# RS485_Reserved_Sensor_Socket.net
KiCad netlist of a schematic drawn in Altium Designer
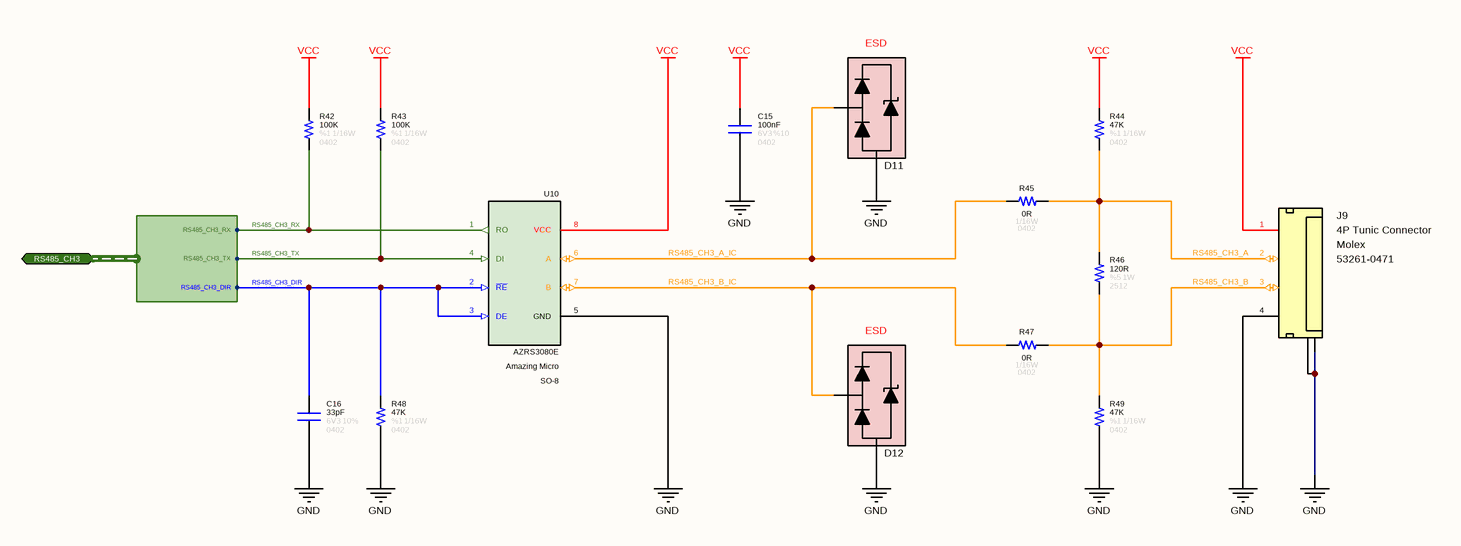
[diagram p0: RS485 Reserved Sensor Socket.SchDoc]

(export (version "E")
  (design (tool "Eeschema 10.0.6"))
  (components
    (comp (ref "C15")
      (value "100nF")
      (footprint "CAPACITOR_0402")
      (description "Capacitor - 100nF [0402-6V3] (Ceramic)")
      (fields
        (field (name "MANUFACTURER PART NUMBER") "04026D104KAT4A")
        (field (name "TOLERANCE") "%10")
        (field (name "VOLTAGE") "6V3")
        (field (name "CASE") "0402")
        (field (name "Comment") "Capacitor - 100nF [0402] (Ceramic)")
      )
      (libsource (lib "P101DA_Library") (part "Capacitor - 100nF [0402-6V3]"))
    )
    (comp (ref "C16")
      (value "33pF")
      (footprint "CAPACITOR_0402")
      (description "Capacitor - 33pF [0402] (Ceramic)")
      (fields
        (field (name "MANUFACTURER PART NUMBER") "C0402C330J9RACAUTO")
        (field (name "TOLERANCE") "10%")
        (field (name "CASE") "0402")
        (field (name "VOLTAGE") "6V3")
      )
      (libsource (lib "P101DA_Library") (part "Capacitor - 33pF [0402-6V3]"))
    )
    (comp (ref "D11")
      (value "0402ESDA-MLP1")
      (footprint "ESD_0402")
      (description "SUPPRESSOR ESD 30VDC 0402 HFREE")
      (libsource (lib "P101DA_Library") (part "Diode - TPD1E05U06DPYR"))
    )
    (comp (ref "D12")
      (value "0402ESDA-MLP1")
      (footprint "ESD_0402")
      (description "SUPPRESSOR ESD 30VDC 0402 HFREE")
      (libsource (lib "P101DA_Library") (part "Diode - TPD1E05U06DPYR"))
    )
    (comp (ref "J9")
      (value "4P SMD Tunic Connector")
      (footprint "Connector_Tunic 4P")
      (description "Mini Tunic Connector with 4P")
      (fields
        (field (name "MANUFACTURER NAME") "Molex")
        (field (name "MANUFACTURER PART NUMBER") "53261-0471")
      )
      (libsource (lib "P101DA_Library") (part "Connector - Mini Tunic 4P (1.25)"))
    )
    (comp (ref "R42")
      (value "100K")
      (footprint "RESISTOR_0402")
      (description "Thick Film Resistors - SMD 1/16 W 100 KOhm 1%")
      (fields
        (field (name "MANUFACTURER PART NUMBER") "CRCW0402100KFKED")
        (field (name "TOLERANCE") "%1")
        (field (name "CASE") "0402")
        (field (name "POWER") "1/16W")
        (field (name "Comment") "100K - 0402 - %1 - 1/16W")
      )
      (libsource (lib "P101DA_Library") (part "Resistor - 100K [0402]"))
    )
    (comp (ref "R43")
      (value "100K")
      (footprint "RESISTOR_0402")
      (description "Thick Film Resistors - SMD 1/16 W 100 KOhm 1%")
      (fields
        (field (name "MANUFACTURER PART NUMBER") "CRCW0402100KFKED")
        (field (name "TOLERANCE") "%1")
        (field (name "CASE") "0402")
        (field (name "POWER") "1/16W")
        (field (name "Comment") "100K - 0402 - %1 - 1/16W")
      )
      (libsource (lib "P101DA_Library") (part "Resistor - 100K [0402]"))
    )
    (comp (ref "R44")
      (value "47K")
      (footprint "RESISTOR_0402")
      (description "Thick Film Resistors - SMD 1/16 W 47 KOhm 1%")
      (fields
        (field (name "MANUFACTURER PART NUMBER") "CRCW040247K0FKED")
        (field (name "TOLERANCE") "%1")
        (field (name "CASE") "0402")
        (field (name "POWER") "1/16W")
        (field (name "Comment") "47K - 0402 - %1 - 1/16W")
      )
      (libsource (lib "P101DA_Library") (part "Resistor - 47K [0402]"))
    )
    (comp (ref "R45")
      (value "0R")
      (footprint "RESISTOR_0402")
      (description "Thick Film Resistors - SMD 1/16 W 0 Ohm")
      (fields
        (field (name "MANUFACTURER PART NUMBER") "CRCW04020000Z0ED")
        (field (name "CASE") "0402")
        (field (name "POWER") "1/16W")
        (field (name "Comment") "0R - 0402 - %1 - 1/16W")
      )
      (libsource (lib "P101DA_Library") (part "Resistor - 0R [0402]"))
    )
    (comp (ref "R46")
      (value "120R")
      (footprint "RESISTOR_2512")
      (description "Thick Film Resistors - SMD 1 W 120 Ohm 5%")
      (fields
        (field (name "MANUFACTURER PART NUMBER") "RC2512JK-07120RL")
        (field (name "TOLERANCE") "%5")
        (field (name "CASE") "2512")
        (field (name "POWER") "1W")
        (field (name "Comment") "120R - 2512 - %5 - 1W")
      )
      (libsource (lib "P101DA_Library") (part "Resistor - 120R [2512]"))
    )
    (comp (ref "R47")
      (value "0R")
      (footprint "RESISTOR_0402")
      (description "Thick Film Resistors - SMD 1/16 W 0 Ohm")
      (fields
        (field (name "MANUFACTURER PART NUMBER") "CRCW04020000Z0ED")
        (field (name "CASE") "0402")
        (field (name "POWER") "1/16W")
        (field (name "Comment") "0R - 0402 - %1 - 1/16W")
      )
      (libsource (lib "P101DA_Library") (part "Resistor - 0R [0402]"))
    )
    (comp (ref "R48")
      (value "47K")
      (footprint "RESISTOR_0402")
      (description "Thick Film Resistors - SMD 1/16 W 47 KOhm 1%")
      (fields
        (field (name "MANUFACTURER PART NUMBER") "CRCW040247K0FKED")
        (field (name "TOLERANCE") "%1")
        (field (name "CASE") "0402")
        (field (name "POWER") "1/16W")
        (field (name "Comment") "47K - 0402 - %1 - 1/16W")
      )
      (libsource (lib "P101DA_Library") (part "Resistor - 47K [0402]"))
    )
    (comp (ref "R49")
      (value "47K")
      (footprint "RESISTOR_0402")
      (description "Thick Film Resistors - SMD 1/16 W 47 KOhm 1%")
      (fields
        (field (name "MANUFACTURER PART NUMBER") "CRCW040247K0FKED")
        (field (name "TOLERANCE") "%1")
        (field (name "CASE") "0402")
        (field (name "POWER") "1/16W")
        (field (name "Comment") "47K - 0402 - %1 - 1/16W")
      )
      (libsource (lib "P101DA_Library") (part "Resistor - 47K [0402]"))
    )
    (comp (ref "U10")
      (value "RS485 Modulator")
      (footprint "SOP-8L (AZRS3080E)")
      (description "Half-duplex RS485 transceiver.")
      (fields
        (field (name "CASE") "SO-8")
        (field (name "MANUFACTURER PART NUMBER") "AZRS3080E")
        (field (name "MANUFACTURER NAME") "Amazing Micro")
      )
      (libsource (lib "P101DA_Library") (part "IC - AZRS3080E"))
    )
  )
  (nets
    (net (code "2") (name "/RS485_CH3_A") (class "Default")
      (node (ref "J9") (pin "2") (pinfunction "Pin-2_2") (pintype "bidirectional"))
      (node (ref "R44") (pin "1") (pinfunction "1_1") (pintype "passive"))
      (node (ref "R45") (pin "1") (pinfunction "1_1") (pintype "passive"))
      (node (ref "R46") (pin "2") (pinfunction "2_2") (pintype "passive"))
    )
    (net (code "3") (name "/RS485_CH3_A_IC") (class "Default")
      (node (ref "D11") (pin "1") (pinfunction "I/O_1") (pintype "passive"))
      (node (ref "R45") (pin "2") (pinfunction "2_2") (pintype "passive"))
      (node (ref "U10") (pin "6") (pinfunction "A_6") (pintype "bidirectional"))
    )
    (net (code "4") (name "/RS485_CH3_B") (class "Default")
      (node (ref "J9") (pin "3") (pinfunction "Pin-3_3") (pintype "bidirectional"))
      (node (ref "R46") (pin "1") (pinfunction "1_1") (pintype "passive"))
      (node (ref "R47") (pin "1") (pinfunction "1_1") (pintype "passive"))
      (node (ref "R49") (pin "2") (pinfunction "2_2") (pintype "passive"))
    )
    (net (code "5") (name "/RS485_CH3_B_IC") (class "Default")
      (node (ref "D12") (pin "1") (pinfunction "I/O_1") (pintype "passive"))
      (node (ref "R47") (pin "2") (pinfunction "2_2") (pintype "passive"))
      (node (ref "U10") (pin "7") (pinfunction "B_7") (pintype "bidirectional"))
    )
    (net (code "6") (name "/RS485_CH3_DIR") (class "Default")
      (node (ref "C16") (pin "2") (pinfunction "2_2") (pintype "passive"))
      (node (ref "R48") (pin "2") (pinfunction "2_2") (pintype "passive"))
      (node (ref "U10") (pin "2") (pinfunction "~{RE}_2") (pintype "input"))
      (node (ref "U10") (pin "3") (pinfunction "DE_3") (pintype "input"))
    )
    (net (code "7") (name "/RS485_CH3_RX") (class "Default")
      (node (ref "R42") (pin "1") (pinfunction "1_1") (pintype "passive"))
      (node (ref "U10") (pin "1") (pinfunction "RO_1") (pintype "output"))
    )
    (net (code "8") (name "/RS485_CH3_TX") (class "Default")
      (node (ref "R43") (pin "1") (pinfunction "1_1") (pintype "passive"))
      (node (ref "U10") (pin "4") (pinfunction "DI_4") (pintype "input"))
    )
    (net (code "10") (name "GND") (class "Default")
      (node (ref "C15") (pin "1") (pinfunction "1_1") (pintype "passive"))
      (node (ref "C16") (pin "1") (pinfunction "1_1") (pintype "passive"))
      (node (ref "D11") (pin "2") (pinfunction "GND_2") (pintype "passive"))
      (node (ref "D12") (pin "2") (pinfunction "GND_2") (pintype "passive"))
      (node (ref "J9") (pin "4") (pinfunction "Pin-4_4") (pintype "power_in"))
      (node (ref "J9") (pin "5") (pinfunction "GND_5") (pintype "passive"))
      (node (ref "J9") (pin "6") (pinfunction "GND_6") (pintype "passive"))
      (node (ref "R48") (pin "1") (pinfunction "1_1") (pintype "passive"))
      (node (ref "R49") (pin "1") (pinfunction "1_1") (pintype "passive"))
      (node (ref "U10") (pin "5") (pinfunction "GND_5") (pintype "passive"))
    )
    (net (code "11") (name "VCC") (class "Default")
      (node (ref "C15") (pin "2") (pinfunction "2_2") (pintype "passive"))
      (node (ref "J9") (pin "1") (pinfunction "Pin-1_1") (pintype "power_in"))
      (node (ref "R42") (pin "2") (pinfunction "2_2") (pintype "passive"))
      (node (ref "R43") (pin "2") (pinfunction "2_2") (pintype "passive"))
      (node (ref "R44") (pin "2") (pinfunction "2_2") (pintype "passive"))
      (node (ref "U10") (pin "8") (pinfunction "VCC_8") (pintype "power_in"))
    )
  )
)
